# BLR.net
KiCad netlist of a schematic drawn in Altium Designer
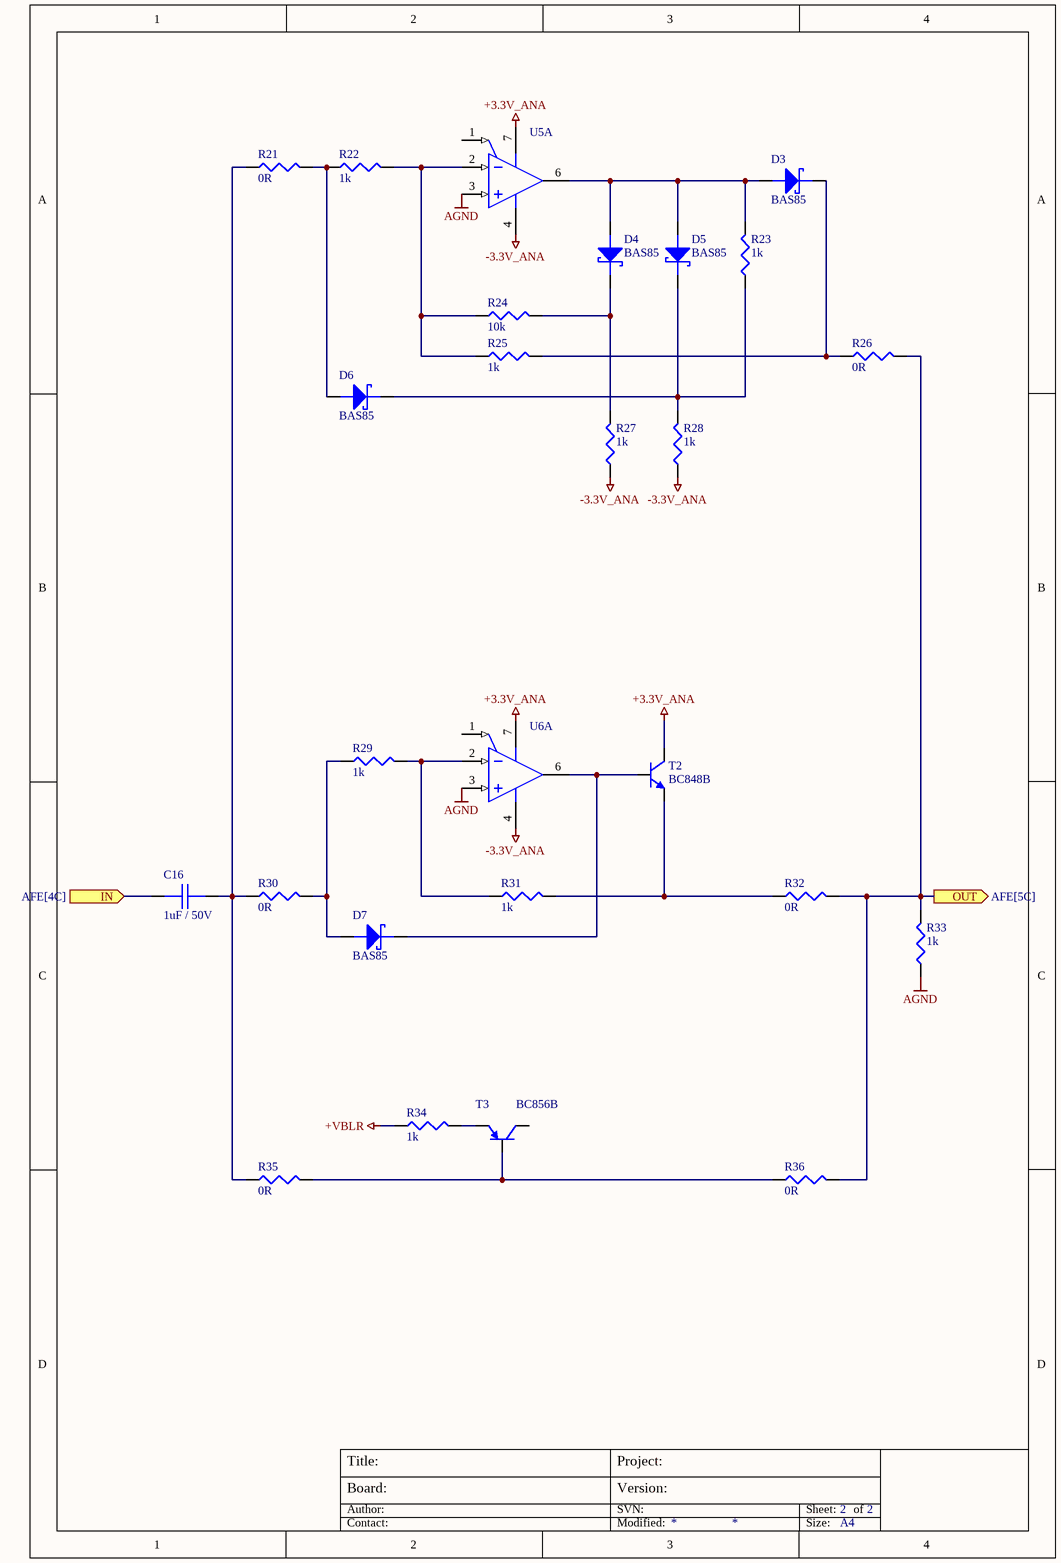
[diagram p0: BLR.SchDoc]

(export (version "E")
  (design (tool "Eeschema 10.0.6"))
  (components
    (comp (ref "C16")
      (value "1uF / 50V")
      (footprint "1206_C")
      (description "1uF 50V X7R")
      (fields (field (name "PART NUMBER") "SMD1206-1uF-50V"))
      (libsource (lib "ALTIUM_DB_LIB") (part "CAP_NONPOL"))
    )
    (comp (ref "D3")
      (value "BAS85")
      (footprint "SOD80")
      (description "Small Signal Schottky Diode, Single, 30 V, 200 mA,  125 °C")
      (libsource (lib "ALTIUM_DB_LIB") (part "DIODE_SCHOTTKY"))
    )
    (comp (ref "D4")
      (value "BAS85")
      (footprint "SOD80")
      (description "Small Signal Schottky Diode, Single, 30 V, 200 mA,  125 °C")
      (libsource (lib "ALTIUM_DB_LIB") (part "DIODE_SCHOTTKY"))
    )
    (comp (ref "D5")
      (value "BAS85")
      (footprint "SOD80")
      (description "Small Signal Schottky Diode, Single, 30 V, 200 mA,  125 °C")
      (libsource (lib "ALTIUM_DB_LIB") (part "DIODE_SCHOTTKY"))
    )
    (comp (ref "D6")
      (value "BAS85")
      (footprint "SOD80")
      (description "Small Signal Schottky Diode, Single, 30 V, 200 mA,  125 °C")
      (libsource (lib "ALTIUM_DB_LIB") (part "DIODE_SCHOTTKY"))
    )
    (comp (ref "D7")
      (value "BAS85")
      (footprint "SOD80")
      (description "Small Signal Schottky Diode, Single, 30 V, 200 mA,  125 °C")
      (libsource (lib "ALTIUM_DB_LIB") (part "DIODE_SCHOTTKY"))
    )
    (comp (ref "R21")
      (value "0R")
      (footprint "1206")
      (description "0R 1206 0.25W 5%")
      (fields (field (name "PART NUMBER") "SMD1206-0R 5%"))
      (libsource (lib "ALTIUM_DB_LIB") (part "RESISTOR"))
    )
    (comp (ref "R22")
      (value "1k")
      (footprint "1206")
      (description "1k 1206 0.25W 5%")
      (fields (field (name "PART NUMBER") "SMD1206-1k 5%"))
      (libsource (lib "ALTIUM_DB_LIB") (part "RESISTOR"))
    )
    (comp (ref "R23")
      (value "1k")
      (footprint "1206")
      (description "1k 1206 0.25W 5%")
      (fields (field (name "PART NUMBER") "SMD1206-1k 5%"))
      (libsource (lib "ALTIUM_DB_LIB") (part "RESISTOR"))
    )
    (comp (ref "R24")
      (value "10k")
      (footprint "1206")
      (description "10k 1206 0.25W 5%")
      (fields (field (name "PART NUMBER") "SMD1206-10k 5%"))
      (libsource (lib "ALTIUM_DB_LIB") (part "RESISTOR"))
    )
    (comp (ref "R25")
      (value "1k")
      (footprint "1206")
      (description "1k 1206 0.25W 5%")
      (fields (field (name "PART NUMBER") "SMD1206-1k 5%"))
      (libsource (lib "ALTIUM_DB_LIB") (part "RESISTOR"))
    )
    (comp (ref "R26")
      (value "0R")
      (footprint "1206")
      (description "0R 1206 0.25W 5%")
      (fields (field (name "PART NUMBER") "SMD1206-0R 5%"))
      (libsource (lib "ALTIUM_DB_LIB") (part "RESISTOR"))
    )
    (comp (ref "R27")
      (value "1k")
      (footprint "1206")
      (description "1k 1206 0.25W 5%")
      (fields (field (name "PART NUMBER") "SMD1206-1k 5%"))
      (libsource (lib "ALTIUM_DB_LIB") (part "RESISTOR"))
    )
    (comp (ref "R28")
      (value "1k")
      (footprint "1206")
      (description "1k 1206 0.25W 5%")
      (fields (field (name "PART NUMBER") "SMD1206-1k 5%"))
      (libsource (lib "ALTIUM_DB_LIB") (part "RESISTOR"))
    )
    (comp (ref "R29")
      (value "1k")
      (footprint "1206")
      (description "1k 1206 0.25W 5%")
      (fields (field (name "PART NUMBER") "SMD1206-1k 5%"))
      (libsource (lib "ALTIUM_DB_LIB") (part "RESISTOR"))
    )
    (comp (ref "R30")
      (value "0R")
      (footprint "1206")
      (description "0R 1206 0.25W 5%")
      (fields (field (name "PART NUMBER") "SMD1206-0R 5%"))
      (libsource (lib "ALTIUM_DB_LIB") (part "RESISTOR"))
    )
    (comp (ref "R31")
      (value "1k")
      (footprint "1206")
      (description "1k 1206 0.25W 5%")
      (fields (field (name "PART NUMBER") "SMD1206-1k 5%"))
      (libsource (lib "ALTIUM_DB_LIB") (part "RESISTOR"))
    )
    (comp (ref "R32")
      (value "0R")
      (footprint "1206")
      (description "0R 1206 0.25W 5%")
      (fields (field (name "PART NUMBER") "SMD1206-0R 5%"))
      (libsource (lib "ALTIUM_DB_LIB") (part "RESISTOR"))
    )
    (comp (ref "R33")
      (value "1k")
      (footprint "1206")
      (description "1k 1206 0.25W 5%")
      (fields (field (name "PART NUMBER") "SMD1206-1k 5%"))
      (libsource (lib "ALTIUM_DB_LIB") (part "RESISTOR"))
    )
    (comp (ref "R34")
      (value "1k")
      (footprint "1206")
      (description "1k 1206 0.25W 5%")
      (fields (field (name "PART NUMBER") "SMD1206-1k 5%"))
      (libsource (lib "ALTIUM_DB_LIB") (part "RESISTOR"))
    )
    (comp (ref "R35")
      (value "0R")
      (footprint "1206")
      (description "0R 1206 0.25W 5%")
      (fields (field (name "PART NUMBER") "SMD1206-0R 5%"))
      (libsource (lib "ALTIUM_DB_LIB") (part "RESISTOR"))
    )
    (comp (ref "R36")
      (value "0R")
      (footprint "1206")
      (description "0R 1206 0.25W 5%")
      (fields (field (name "PART NUMBER") "SMD1206-0R 5%"))
      (libsource (lib "ALTIUM_DB_LIB") (part "RESISTOR"))
    )
    (comp (ref "T2")
      (value "BC848B")
      (footprint "SOT-23")
      (description "Bipolar (BJT) Single Transistor, NPN, 30 V, 100 mA, 300 mW, SOT-23, Surface Mount")
      (libsource (lib "ALTIUM_DB_LIB") (part "BJT_NPN"))
    )
    (comp (ref "T3")
      (value "BC856B")
      (footprint "SOT-23")
      (description "BC856B Bipolar (BJT) Single Transistor, PNP, 65 V, 100 mA, 250 mW, SOT-23, Surface Mount")
      (libsource (lib "ALTIUM_DB_LIB") (part "BJT_PNP"))
    )
    (comp (ref "U5")
      (value "LT1806CS8#PBF")
      (footprint "SO-8")
      (fields
        (field (name "MANUFACTURER") "Linear Technology")
        (field (name "LINEAR TECHNOLOGY PART NUMBER") "LT1806")
      )
      (libsource (lib "ALTIUM_DB_LIB") (part "LT1806CS8#PBF"))
    )
    (comp (ref "U6")
      (value "LT1806CS8#PBF")
      (footprint "SO-8")
      (fields
        (field (name "MANUFACTURER") "Linear Technology")
        (field (name "LINEAR TECHNOLOGY PART NUMBER") "LT1806")
      )
      (libsource (lib "ALTIUM_DB_LIB") (part "LT1806CS8#PBF"))
    )
  )
  (nets
    (net (code "1") (name "+3.3V_ANA") (class "Default")
      (node (ref "T2") (pin "3") (pinfunction "C_3") (pintype "passive"))
      (node (ref "U5") (pin "7") (pinfunction "V+_7") (pintype "power_in"))
      (node (ref "U6") (pin "7") (pinfunction "V+_7") (pintype "power_in"))
    )
    (net (code "2") (name "+VBLR") (class "Default") (node (ref "R34") (pin "1") (pintype "passive")))
    (net (code "3") (name "-3.3V_ANA") (class "Default")
      (node (ref "R27") (pin "1") (pintype "passive"))
      (node (ref "R28") (pin "1") (pintype "passive"))
      (node (ref "U5") (pin "4") (pinfunction "V-_4") (pintype "power_in"))
      (node (ref "U6") (pin "4") (pinfunction "V-_4") (pintype "power_in"))
    )
    (net (code "4") (name "/IN") (class "Default") (node (ref "C16") (pin "1") (pintype "passive")))
    (net (code "5") (name "/OUT") (class "Default")
      (node (ref "R26") (pin "2") (pintype "passive"))
      (node (ref "R32") (pin "2") (pintype "passive"))
      (node (ref "R33") (pin "2") (pintype "passive"))
      (node (ref "R36") (pin "2") (pintype "passive"))
    )
    (net (code "6") (name "AGND") (class "Default")
      (node (ref "R33") (pin "1") (pintype "passive"))
      (node (ref "U5") (pin "3") (pinfunction "+IN_3") (pintype "input"))
      (node (ref "U6") (pin "3") (pinfunction "+IN_3") (pintype "input"))
    )
    (net (code "7") (name "Net-(C16-Pad2)") (class "Default")
      (node (ref "C16") (pin "2") (pintype "passive"))
      (node (ref "R21") (pin "1") (pintype "passive"))
      (node (ref "R30") (pin "1") (pintype "passive"))
      (node (ref "R35") (pin "1") (pintype "passive"))
    )
    (net (code "8") (name "Net-(D3-PadK)") (class "Default")
      (node (ref "D3") (pin "K") (pinfunction "K_K") (pintype "passive"))
      (node (ref "R25") (pin "2") (pintype "passive"))
      (node (ref "R26") (pin "1") (pintype "passive"))
    )
    (net (code "9") (name "Net-(D4-PadK)") (class "Default")
      (node (ref "D4") (pin "K") (pinfunction "K_K") (pintype "passive"))
      (node (ref "R24") (pin "2") (pintype "passive"))
      (node (ref "R27") (pin "2") (pintype "passive"))
    )
    (net (code "10") (name "Net-(D5-PadK)") (class "Default")
      (node (ref "D5") (pin "K") (pinfunction "K_K") (pintype "passive"))
      (node (ref "D6") (pin "K") (pinfunction "K_K") (pintype "passive"))
      (node (ref "R23") (pin "1") (pintype "passive"))
      (node (ref "R28") (pin "2") (pintype "passive"))
    )
    (net (code "11") (name "Net-(D6-PadA)") (class "Default")
      (node (ref "D6") (pin "A") (pinfunction "A_A") (pintype "passive"))
      (node (ref "R21") (pin "2") (pintype "passive"))
      (node (ref "R22") (pin "1") (pintype "passive"))
    )
    (net (code "12") (name "Net-(D7-PadA)") (class "Default")
      (node (ref "D7") (pin "A") (pinfunction "A_A") (pintype "passive"))
      (node (ref "R29") (pin "1") (pintype "passive"))
      (node (ref "R30") (pin "2") (pintype "passive"))
    )
    (net (code "13") (name "Net-(T2-B)") (class "Default")
      (node (ref "D7") (pin "K") (pinfunction "K_K") (pintype "passive"))
      (node (ref "T2") (pin "1") (pinfunction "B_1") (pintype "passive"))
      (node (ref "U6") (pin "6") (pinfunction "OUT_6") (pintype "tri_state"))
    )
    (net (code "14") (name "Net-(T2-E)") (class "Default")
      (node (ref "R31") (pin "2") (pintype "passive"))
      (node (ref "R32") (pin "1") (pintype "passive"))
      (node (ref "T2") (pin "2") (pinfunction "E_2") (pintype "passive"))
    )
    (net (code "15") (name "Net-(T3-B)") (class "Default")
      (node (ref "R35") (pin "2") (pintype "passive"))
      (node (ref "R36") (pin "1") (pintype "passive"))
      (node (ref "T3") (pin "1") (pinfunction "B_1") (pintype "passive"))
    )
    (net (code "16") (name "Net-(T3-E)") (class "Default")
      (node (ref "R34") (pin "2") (pintype "passive"))
      (node (ref "T3") (pin "2") (pinfunction "E_2") (pintype "passive"))
    )
    (net (code "17") (name "Net-(U5A--IN)") (class "Default")
      (node (ref "R22") (pin "2") (pintype "passive"))
      (node (ref "R24") (pin "1") (pintype "passive"))
      (node (ref "R25") (pin "1") (pintype "passive"))
      (node (ref "U5") (pin "2") (pinfunction "-IN_2") (pintype "input"))
    )
    (net (code "18") (name "Net-(U5A-OUT)") (class "Default")
      (node (ref "D3") (pin "A") (pinfunction "A_A") (pintype "passive"))
      (node (ref "D4") (pin "A") (pinfunction "A_A") (pintype "passive"))
      (node (ref "D5") (pin "A") (pinfunction "A_A") (pintype "passive"))
      (node (ref "R23") (pin "2") (pintype "passive"))
      (node (ref "U5") (pin "6") (pinfunction "OUT_6") (pintype "tri_state"))
    )
    (net (code "19") (name "Net-(U6A--IN)") (class "Default")
      (node (ref "R29") (pin "2") (pintype "passive"))
      (node (ref "R31") (pin "1") (pintype "passive"))
      (node (ref "U6") (pin "2") (pinfunction "-IN_2") (pintype "input"))
    )
    (net (code "20") (name "unconnected-(T3-C-Pad3)") (class "Default")
      (node (ref "T3") (pin "3") (pinfunction "C_3") (pintype "passive"))
    )
    (net (code "21") (name "unconnected-(U5A-~{SHDN}-Pad1)") (class "Default")
      (node (ref "U5") (pin "1") (pinfunction "~{SHDN}_1") (pintype "input"))
    )
    (net (code "22") (name "unconnected-(U6A-~{SHDN}-Pad1)") (class "Default")
      (node (ref "U6") (pin "1") (pinfunction "~{SHDN}_1") (pintype "input"))
    )
  )
)
